# StatusLEDSchem.net
KiCad netlist of a schematic drawn in Altium Designer
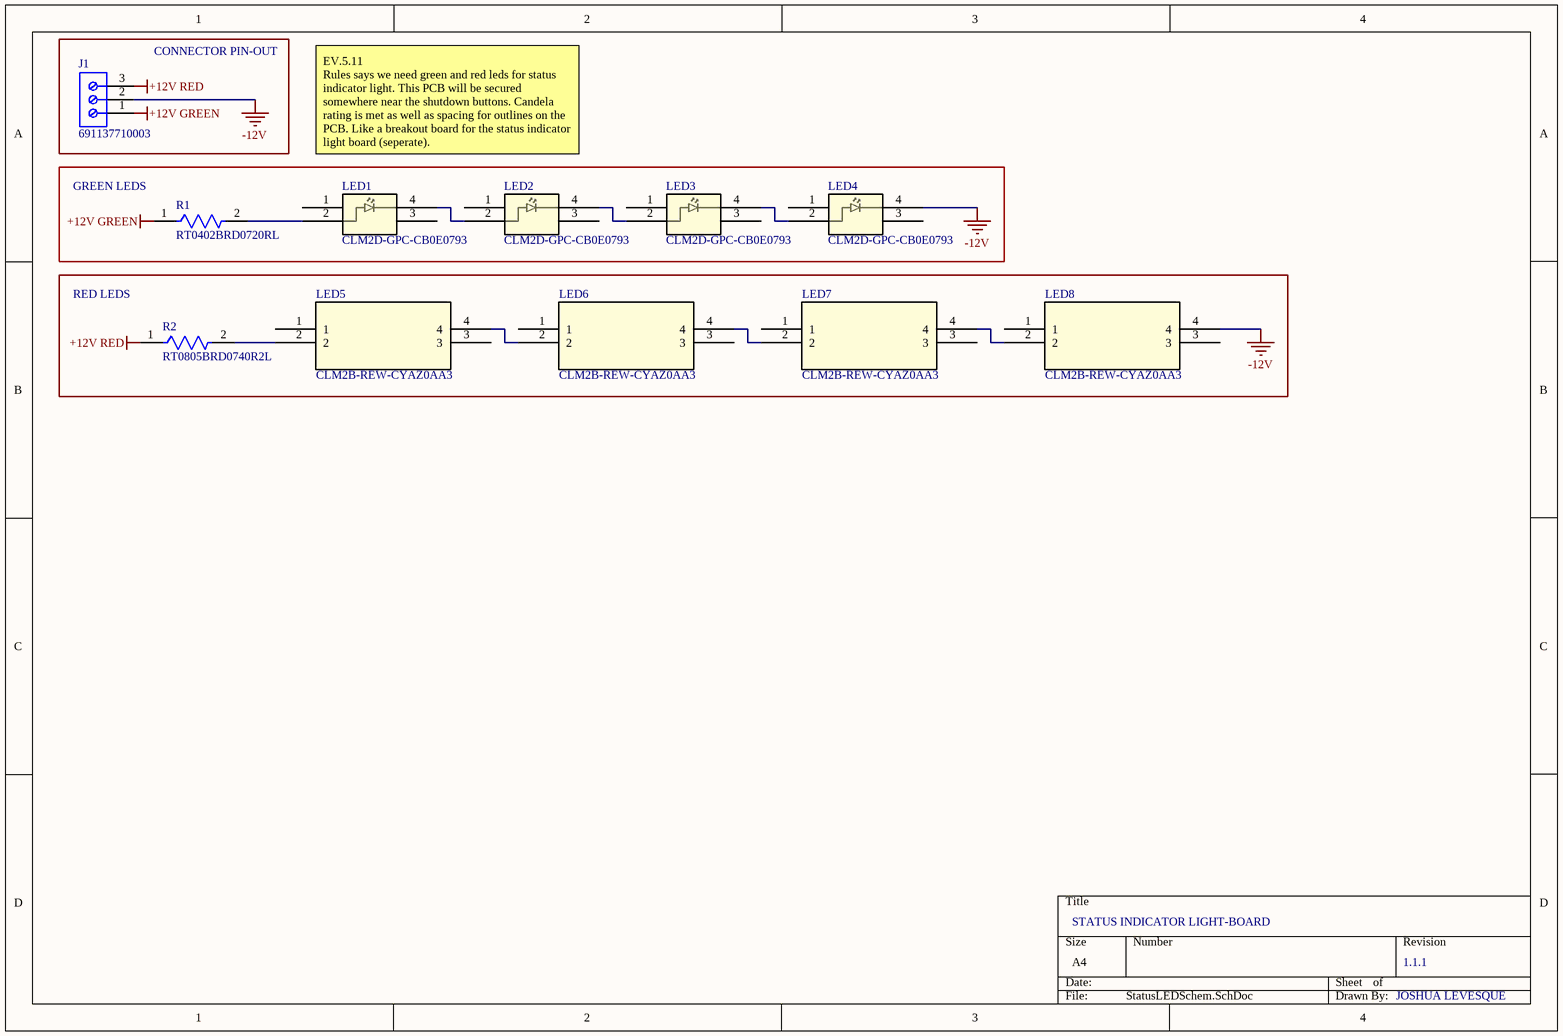
[diagram p0: StatusLEDSchem.SchDoc]

(export (version "E")
  (design (tool "Eeschema 10.0.6"))
  (components
    (comp (ref "J1")
      (value "691137710003")
      (footprint "691137710003")
      (libsource (lib "Altium Content Vault") (part "TBL - 1R - 03P - Screw"))
    )
    (comp (ref "LED1")
      (value "CLM2D-GPC-CB0E0793")
      (footprint "PLCC4_3.5X2.8X3.45_CRW")
      (description "No Description Available")
      (libsource (lib "CLM2D-GPC-CB0E0793") (part "CLM2D-GPC-CB0E0793"))
    )
    (comp (ref "LED2")
      (value "CLM2D-GPC-CB0E0793")
      (footprint "PLCC4_3.5X2.8X3.45_CRW")
      (description "No Description Available")
      (libsource (lib "CLM2D-GPC-CB0E0793") (part "CLM2D-GPC-CB0E0793"))
    )
    (comp (ref "LED3")
      (value "CLM2D-GPC-CB0E0793")
      (footprint "PLCC4_3.5X2.8X3.45_CRW")
      (description "No Description Available")
      (libsource (lib "CLM2D-GPC-CB0E0793") (part "CLM2D-GPC-CB0E0793"))
    )
    (comp (ref "LED4")
      (value "CLM2D-GPC-CB0E0793")
      (footprint "PLCC4_3.5X2.8X3.45_CRW")
      (description "No Description Available")
      (libsource (lib "CLM2D-GPC-CB0E0793") (part "CLM2D-GPC-CB0E0793"))
    )
    (comp (ref "LED5")
      (value "CLM2B-REW-CYAZ0AA3")
      (footprint "PLCC4_CLM2B_3P2X2P7_CRE")
      (description "No Description Available")
      (libsource (lib "CLM2B-REW-CYAZ0AA3") (part "CLM2B-REW-CYAZ0AA3"))
    )
    (comp (ref "LED6")
      (value "CLM2B-REW-CYAZ0AA3")
      (footprint "PLCC4_CLM2B_3P2X2P7_CRE")
      (description "No Description Available")
      (libsource (lib "CLM2B-REW-CYAZ0AA3") (part "CLM2B-REW-CYAZ0AA3"))
    )
    (comp (ref "LED7")
      (value "CLM2B-REW-CYAZ0AA3")
      (footprint "PLCC4_CLM2B_3P2X2P7_CRE")
      (description "No Description Available")
      (libsource (lib "CLM2B-REW-CYAZ0AA3") (part "CLM2B-REW-CYAZ0AA3"))
    )
    (comp (ref "LED8")
      (value "CLM2B-REW-CYAZ0AA3")
      (footprint "PLCC4_CLM2B_3P2X2P7_CRE")
      (description "No Description Available")
      (libsource (lib "CLM2B-REW-CYAZ0AA3") (part "CLM2B-REW-CYAZ0AA3"))
    )
    (comp (ref "R1")
      (value "RT0402BRD0720RL")
      (footprint "FP-RT0402-0_35-MFG")
      (description "RES SMD 20 OHM 0.1% 1/16W 0402")
      (fields (field (name "TOLERANCE") "0.1%"))
      (libsource (lib "Altium Content Vault") (part "1029c3af85768c4190bb7ad29bc67b5"))
    )
    (comp (ref "R2")
      (value "RT0805BRD0740R2L")
      (footprint "FP-RT0805-MFG")
      (description "RES SMD 40.2 OHM 0.1% 1/8W 0805")
      (fields
        (field (name "MANUFACTURER") "Yageo")
        (field (name "OCTOPART") "https://octopart.com/rt0805brd0740r2l-yageo-1269193")
      )
      (libsource (lib "Altium Content Vault") (part "1029c3af85768c4190bb7ad29bc67b5"))
    )
  )
  (nets
    (net (code "1") (name "+12V GREEN") (class "Default")
      (node (ref "J1") (pin "1") (pinfunction "1_1") (pintype "passive"))
      (node (ref "R1") (pin "1") (pinfunction "1_1") (pintype "passive"))
    )
    (net (code "2") (name "+12V RED") (class "Default")
      (node (ref "J1") (pin "3") (pinfunction "3_3") (pintype "passive"))
      (node (ref "R2") (pin "1") (pinfunction "1_1") (pintype "passive"))
    )
    (net (code "3") (name "-12V") (class "Default")
      (node (ref "J1") (pin "2") (pinfunction "2_2") (pintype "passive"))
      (node (ref "LED4") (pin "4") (pinfunction "4_4") (pintype "passive"))
      (node (ref "LED8") (pin "4") (pinfunction "4_4") (pintype "passive"))
    )
    (net (code "4") (name "Net-(LED1-Pad2)") (class "Default")
      (node (ref "LED1") (pin "2") (pinfunction "2_2") (pintype "passive"))
      (node (ref "R1") (pin "2") (pinfunction "2_2") (pintype "passive"))
    )
    (net (code "5") (name "Net-(LED1-Pad4)") (class "Default")
      (node (ref "LED1") (pin "4") (pinfunction "4_4") (pintype "passive"))
      (node (ref "LED2") (pin "2") (pinfunction "2_2") (pintype "passive"))
    )
    (net (code "6") (name "Net-(LED2-Pad4)") (class "Default")
      (node (ref "LED2") (pin "4") (pinfunction "4_4") (pintype "passive"))
      (node (ref "LED3") (pin "2") (pinfunction "2_2") (pintype "passive"))
    )
    (net (code "7") (name "Net-(LED3-Pad4)") (class "Default")
      (node (ref "LED3") (pin "4") (pinfunction "4_4") (pintype "passive"))
      (node (ref "LED4") (pin "2") (pinfunction "2_2") (pintype "passive"))
    )
    (net (code "8") (name "Net-(LED5-Pad2)") (class "Default")
      (node (ref "LED5") (pin "2") (pinfunction "2_2") (pintype "passive"))
      (node (ref "R2") (pin "2") (pinfunction "2_2") (pintype "passive"))
    )
    (net (code "9") (name "Net-(LED5-Pad4)") (class "Default")
      (node (ref "LED5") (pin "4") (pinfunction "4_4") (pintype "passive"))
      (node (ref "LED6") (pin "2") (pinfunction "2_2") (pintype "passive"))
    )
    (net (code "10") (name "Net-(LED6-Pad4)") (class "Default")
      (node (ref "LED6") (pin "4") (pinfunction "4_4") (pintype "passive"))
      (node (ref "LED7") (pin "2") (pinfunction "2_2") (pintype "passive"))
    )
    (net (code "11") (name "Net-(LED7-Pad4)") (class "Default")
      (node (ref "LED7") (pin "4") (pinfunction "4_4") (pintype "passive"))
      (node (ref "LED8") (pin "2") (pinfunction "2_2") (pintype "passive"))
    )
    (net (code "12") (name "unconnected-(LED1-Pad1)") (class "Default")
      (node (ref "LED1") (pin "1") (pinfunction "1_1") (pintype "passive"))
    )
    (net (code "13") (name "unconnected-(LED1-Pad3)") (class "Default")
      (node (ref "LED1") (pin "3") (pinfunction "3_3") (pintype "passive"))
    )
    (net (code "14") (name "unconnected-(LED2-Pad1)") (class "Default")
      (node (ref "LED2") (pin "1") (pinfunction "1_1") (pintype "passive"))
    )
    (net (code "15") (name "unconnected-(LED2-Pad3)") (class "Default")
      (node (ref "LED2") (pin "3") (pinfunction "3_3") (pintype "passive"))
    )
    (net (code "16") (name "unconnected-(LED3-Pad1)") (class "Default")
      (node (ref "LED3") (pin "1") (pinfunction "1_1") (pintype "passive"))
    )
    (net (code "17") (name "unconnected-(LED3-Pad3)") (class "Default")
      (node (ref "LED3") (pin "3") (pinfunction "3_3") (pintype "passive"))
    )
    (net (code "18") (name "unconnected-(LED4-Pad1)") (class "Default")
      (node (ref "LED4") (pin "1") (pinfunction "1_1") (pintype "passive"))
    )
    (net (code "19") (name "unconnected-(LED4-Pad3)") (class "Default")
      (node (ref "LED4") (pin "3") (pinfunction "3_3") (pintype "passive"))
    )
    (net (code "20") (name "unconnected-(LED5-Pad1)") (class "Default")
      (node (ref "LED5") (pin "1") (pinfunction "1_1") (pintype "passive"))
    )
    (net (code "21") (name "unconnected-(LED5-Pad3)") (class "Default")
      (node (ref "LED5") (pin "3") (pinfunction "3_3") (pintype "passive"))
    )
    (net (code "22") (name "unconnected-(LED6-Pad1)") (class "Default")
      (node (ref "LED6") (pin "1") (pinfunction "1_1") (pintype "passive"))
    )
    (net (code "23") (name "unconnected-(LED6-Pad3)") (class "Default")
      (node (ref "LED6") (pin "3") (pinfunction "3_3") (pintype "passive"))
    )
    (net (code "24") (name "unconnected-(LED7-Pad1)") (class "Default")
      (node (ref "LED7") (pin "1") (pinfunction "1_1") (pintype "passive"))
    )
    (net (code "25") (name "unconnected-(LED7-Pad3)") (class "Default")
      (node (ref "LED7") (pin "3") (pinfunction "3_3") (pintype "passive"))
    )
    (net (code "26") (name "unconnected-(LED8-Pad1)") (class "Default")
      (node (ref "LED8") (pin "1") (pinfunction "1_1") (pintype "passive"))
    )
    (net (code "27") (name "unconnected-(LED8-Pad3)") (class "Default")
      (node (ref "LED8") (pin "3") (pinfunction "3_3") (pintype "passive"))
    )
  )
)
